# eSolderControl_v3.net
KiCad netlist of a schematic drawn in Altium Designer
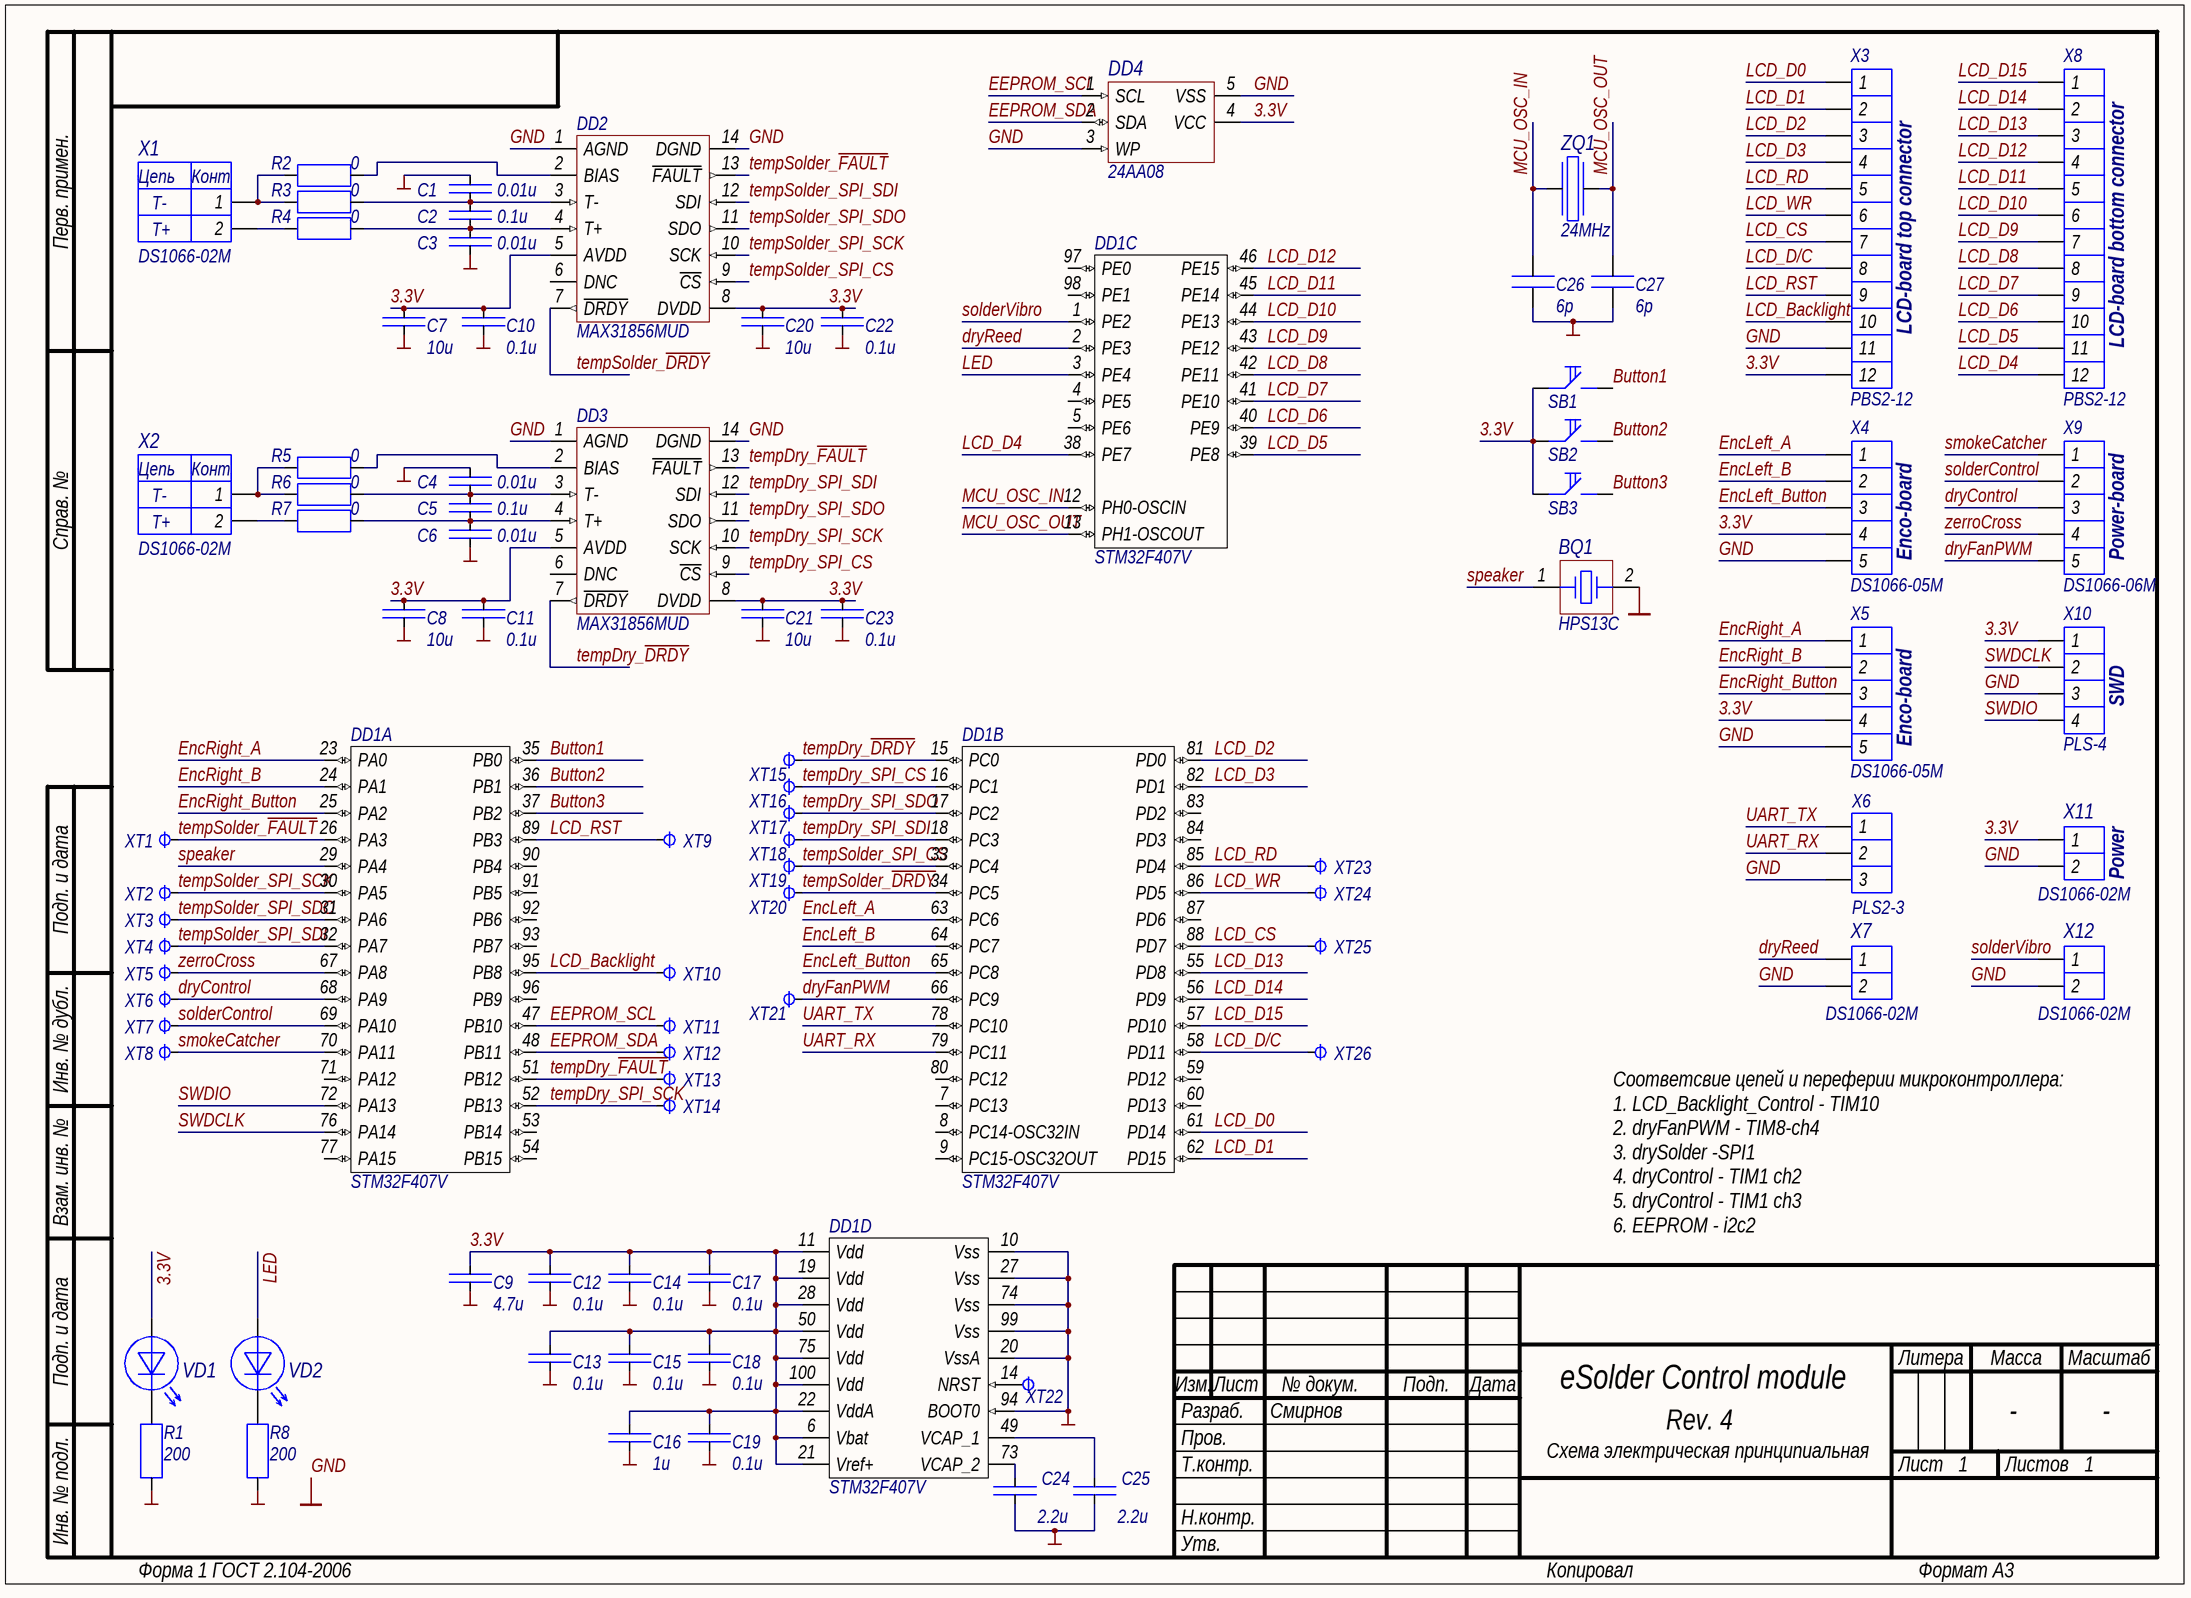
[diagram p0: eSolderControl_v3.SchDoc]

(export (version "E")
  (design (tool "Eeschema 10.0.6"))
  (components
    (comp (ref "BQ1")
      (value "HPS13C")
      (footprint "speaker:HPS13C")
      (libsource (lib "speaker") (part "Buzzer"))
    )
    (comp (ref "C1")
      (value "0.01u")
      (footprint "CapSMD:C0603")
      (libsource (lib "Capasitors") (part "Capasitor"))
    )
    (comp (ref "C2")
      (value "0.1u")
      (footprint "CapSMD:C0603")
      (libsource (lib "Capasitors") (part "Capasitor"))
    )
    (comp (ref "C3")
      (value "0.01u")
      (footprint "CapSMD:C0603")
      (libsource (lib "Capasitors") (part "Capasitor"))
    )
    (comp (ref "C4")
      (value "0.01u")
      (footprint "CapSMD:C0603")
      (libsource (lib "Capasitors") (part "Capasitor"))
    )
    (comp (ref "C5")
      (value "0.1u")
      (footprint "CapSMD:C0603")
      (libsource (lib "Capasitors") (part "Capasitor"))
    )
    (comp (ref "C6")
      (value "0.01u")
      (footprint "CapSMD:C0603")
      (libsource (lib "Capasitors") (part "Capasitor"))
    )
    (comp (ref "C7")
      (value "10u")
      (footprint "CapSMD:C0603")
      (libsource (lib "Capasitors") (part "Capasitor"))
    )
    (comp (ref "C8")
      (value "10u")
      (footprint "CapSMD:C0603")
      (libsource (lib "Capasitors") (part "Capasitor"))
    )
    (comp (ref "C9")
      (value "4.7u")
      (footprint "CapSMD:C0603")
      (libsource (lib "Capasitors") (part "Capasitor"))
    )
    (comp (ref "C10")
      (value "0.1u")
      (footprint "CapSMD:C0603")
      (libsource (lib "Capasitors") (part "Capasitor"))
    )
    (comp (ref "C11")
      (value "0.1u")
      (footprint "CapSMD:C0603")
      (libsource (lib "Capasitors") (part "Capasitor"))
    )
    (comp (ref "C12")
      (value "0.1u")
      (footprint "CapSMD:C0603")
      (libsource (lib "Capasitors") (part "Capasitor"))
    )
    (comp (ref "C13")
      (value "0.1u")
      (footprint "CapSMD:C0603")
      (libsource (lib "Capasitors") (part "Capasitor"))
    )
    (comp (ref "C14")
      (value "0.1u")
      (footprint "CapSMD:C0603")
      (libsource (lib "Capasitors") (part "Capasitor"))
    )
    (comp (ref "C15")
      (value "0.1u")
      (footprint "CapSMD:C0603")
      (libsource (lib "Capasitors") (part "Capasitor"))
    )
    (comp (ref "C16")
      (value "1u")
      (footprint "CapSMD:C0603")
      (libsource (lib "Capasitors") (part "Capasitor"))
    )
    (comp (ref "C17")
      (value "0.1u")
      (footprint "CapSMD:C0603")
      (libsource (lib "Capasitors") (part "Capasitor"))
    )
    (comp (ref "C18")
      (value "0.1u")
      (footprint "CapSMD:C0603")
      (libsource (lib "Capasitors") (part "Capasitor"))
    )
    (comp (ref "C19")
      (value "0.1u")
      (footprint "CapSMD:C0603")
      (libsource (lib "Capasitors") (part "Capasitor"))
    )
    (comp (ref "C20")
      (value "10u")
      (footprint "CapSMD:C0603")
      (libsource (lib "Capasitors") (part "Capasitor"))
    )
    (comp (ref "C21")
      (value "10u")
      (footprint "CapSMD:C0603")
      (libsource (lib "Capasitors") (part "Capasitor"))
    )
    (comp (ref "C22")
      (value "0.1u")
      (footprint "CapSMD:C0603")
      (libsource (lib "Capasitors") (part "Capasitor"))
    )
    (comp (ref "C23")
      (value "0.1u")
      (footprint "CapSMD:C0603")
      (libsource (lib "Capasitors") (part "Capasitor"))
    )
    (comp (ref "C24")
      (value "2.2u")
      (footprint "CapSMD:C0603")
      (libsource (lib "Capasitors") (part "Capasitor"))
    )
    (comp (ref "C25")
      (value "2.2u")
      (footprint "CapSMD:C0603")
      (libsource (lib "Capasitors") (part "Capasitor"))
    )
    (comp (ref "C26") (value "6p") (footprint "CapSMD:C0603") (libsource (lib "") (part "Capasitor_1")))
    (comp (ref "C27") (value "6p") (footprint "CapSMD:C0603") (libsource (lib "") (part "Capasitor_1")))
    (comp (ref "DD1")
      (value "STM32F407V")
      (footprint "STM32:LQFP100")
      (description "100pins, 168MHz")
      (libsource (lib "STM32") (part "STM32F407V"))
    )
    (comp (ref "DD2")
      (value "MAX31856MUD")
      (footprint "TSSOP:TSSOP65P640X120-14N")
      (libsource (lib "ThermocoupleDrv") (part "MAX31856MUD"))
    )
    (comp (ref "DD3")
      (value "MAX31856MUD")
      (footprint "TSSOP:TSSOP65P640X120-14N")
      (libsource (lib "ThermocoupleDrv") (part "MAX31856MUD"))
    )
    (comp (ref "DD4")
      (value "24AA08")
      (footprint "SOT23:SOT95P245X145-5N")
      (description "8K I2C Serial EEPROM")
      (libsource (lib "eeprom") (part "24AA08"))
    )
    (comp (ref "R1")
      (value "200")
      (footprint "ResistorSMD:R0603")
      (libsource (lib "Resistors") (part "Resistor"))
    )
    (comp (ref "R2")
      (value "0")
      (footprint "ResistorSMD:R0603")
      (libsource (lib "Resistors") (part "Resistor"))
    )
    (comp (ref "R3")
      (value "0")
      (footprint "ResistorSMD:R0603")
      (libsource (lib "Resistors") (part "Resistor"))
    )
    (comp (ref "R4")
      (value "0")
      (footprint "ResistorSMD:R0603")
      (libsource (lib "Resistors") (part "Resistor"))
    )
    (comp (ref "R5")
      (value "0")
      (footprint "ResistorSMD:R0603")
      (libsource (lib "Resistors") (part "Resistor"))
    )
    (comp (ref "R6")
      (value "0")
      (footprint "ResistorSMD:R0603")
      (libsource (lib "Resistors") (part "Resistor"))
    )
    (comp (ref "R7")
      (value "0")
      (footprint "ResistorSMD:R0603")
      (libsource (lib "Resistors") (part "Resistor"))
    )
    (comp (ref "R8")
      (value "200")
      (footprint "ResistorSMD:R0603")
      (libsource (lib "Resistors") (part "Resistor"))
    )
    (comp (ref "SB1") (value "*") (footprint "Buttons:TS_6x6") (libsource (lib "Buttons") (part "Button")))
    (comp (ref "SB2") (value "*") (footprint "Buttons:TS_6x6") (libsource (lib "Buttons") (part "Button")))
    (comp (ref "SB3") (value "*") (footprint "Buttons:TS_6x6") (libsource (lib "Buttons") (part "Button")))
    (comp (ref "VD1") (value "*") (footprint "Led:LED 0603_Green") (libsource (lib "LED") (part "LED")))
    (comp (ref "VD2") (value "*") (footprint "Led:LED 0603_RED") (libsource (lib "LED") (part "LED")))
    (comp (ref "X1")
      (value "DS1066-02M")
      (footprint "Connectors:DS1066-02M")
      (libsource (lib "Connectors") (part "2-PIN"))
    )
    (comp (ref "X2")
      (value "DS1066-02M")
      (footprint "Connectors:DS1066-02M")
      (libsource (lib "Connectors") (part "2-PIN"))
    )
    (comp (ref "X3")
      (value "PBS2-12")
      (footprint "Connectors:PBS2-12")
      (libsource (lib "Connectors") (part "12-PIN"))
    )
    (comp (ref "X4")
      (value "DS1066-05M")
      (footprint "Connectors:DS1066-05M")
      (libsource (lib "Connectors") (part "5-PIN"))
    )
    (comp (ref "X5")
      (value "DS1066-05M")
      (footprint "Connectors:DS1066-05M")
      (libsource (lib "Connectors") (part "5-PIN"))
    )
    (comp (ref "X6")
      (value "PLS2-3")
      (footprint "Connectors:PLS2-3")
      (libsource (lib "Connectors") (part "3-PIN"))
    )
    (comp (ref "X7")
      (value "DS1066-02M")
      (footprint "Connectors:DS1066-02M")
      (libsource (lib "Connectors") (part "2-PIN"))
    )
    (comp (ref "X8")
      (value "PBS2-12")
      (footprint "Connectors:PBS2-12")
      (libsource (lib "Connectors") (part "12-PIN"))
    )
    (comp (ref "X9")
      (value "DS1066-06M")
      (footprint "Connectors:DS1066-05M")
      (libsource (lib "Connectors") (part "5-PIN"))
    )
    (comp (ref "X10")
      (value "PLS-4")
      (footprint "Connectors:PLS-4")
      (libsource (lib "Connectors") (part "4-PIN"))
    )
    (comp (ref "X11")
      (value "DS1066-02M")
      (footprint "Connectors:DS1066-02M")
      (libsource (lib "Connectors") (part "2-PIN"))
    )
    (comp (ref "X12")
      (value "DS1066-02M")
      (footprint "Connectors:DS1066-02M")
      (libsource (lib "Connectors") (part "2-PIN"))
    )
    (comp (ref "XT1")
      (value "CheckPoint")
      (footprint "CheckPoint:CheckPoint_2mm")
      (libsource (lib "checkPoint") (part "CheckPoint"))
    )
    (comp (ref "XT2")
      (value "CheckPoint")
      (footprint "CheckPoint:CheckPoint_2mm")
      (libsource (lib "checkPoint") (part "CheckPoint"))
    )
    (comp (ref "XT3")
      (value "CheckPoint")
      (footprint "CheckPoint:CheckPoint_2mm")
      (libsource (lib "checkPoint") (part "CheckPoint"))
    )
    (comp (ref "XT4")
      (value "CheckPoint")
      (footprint "CheckPoint:CheckPoint_2mm")
      (libsource (lib "checkPoint") (part "CheckPoint"))
    )
    (comp (ref "XT5")
      (value "CheckPoint")
      (footprint "CheckPoint:CheckPoint_2mm")
      (libsource (lib "checkPoint") (part "CheckPoint"))
    )
    (comp (ref "XT6")
      (value "CheckPoint")
      (footprint "CheckPoint:CheckPoint_2mm")
      (libsource (lib "checkPoint") (part "CheckPoint"))
    )
    (comp (ref "XT7")
      (value "CheckPoint")
      (footprint "CheckPoint:CheckPoint_2mm")
      (libsource (lib "checkPoint") (part "CheckPoint"))
    )
    (comp (ref "XT8")
      (value "CheckPoint")
      (footprint "CheckPoint:CheckPoint_2mm")
      (libsource (lib "checkPoint") (part "CheckPoint"))
    )
    (comp (ref "XT9")
      (value "CheckPoint")
      (footprint "CheckPoint:CheckPoint_2mm")
      (libsource (lib "checkPoint") (part "CheckPoint"))
    )
    (comp (ref "XT10")
      (value "CheckPoint")
      (footprint "CheckPoint:CheckPoint_2mm")
      (libsource (lib "checkPoint") (part "CheckPoint"))
    )
    (comp (ref "XT11")
      (value "CheckPoint")
      (footprint "CheckPoint:CheckPoint_2mm")
      (libsource (lib "checkPoint") (part "CheckPoint"))
    )
    (comp (ref "XT12")
      (value "CheckPoint")
      (footprint "CheckPoint:CheckPoint_2mm")
      (libsource (lib "checkPoint") (part "CheckPoint"))
    )
    (comp (ref "XT13")
      (value "CheckPoint")
      (footprint "CheckPoint:CheckPoint_2mm")
      (libsource (lib "checkPoint") (part "CheckPoint"))
    )
    (comp (ref "XT14")
      (value "CheckPoint")
      (footprint "CheckPoint:CheckPoint_2mm")
      (libsource (lib "checkPoint") (part "CheckPoint"))
    )
    (comp (ref "XT15")
      (value "CheckPoint")
      (footprint "CheckPoint:CheckPoint_2mm")
      (libsource (lib "checkPoint") (part "CheckPoint"))
    )
    (comp (ref "XT16")
      (value "CheckPoint")
      (footprint "CheckPoint:CheckPoint_2mm")
      (libsource (lib "checkPoint") (part "CheckPoint"))
    )
    (comp (ref "XT17")
      (value "CheckPoint")
      (footprint "CheckPoint:CheckPoint_2mm")
      (libsource (lib "checkPoint") (part "CheckPoint"))
    )
    (comp (ref "XT18")
      (value "CheckPoint")
      (footprint "CheckPoint:CheckPoint_2mm")
      (libsource (lib "checkPoint") (part "CheckPoint"))
    )
    (comp (ref "XT19")
      (value "CheckPoint")
      (footprint "CheckPoint:CheckPoint_2mm")
      (libsource (lib "checkPoint") (part "CheckPoint"))
    )
    (comp (ref "XT20")
      (value "CheckPoint")
      (footprint "CheckPoint:CheckPoint_2mm")
      (libsource (lib "checkPoint") (part "CheckPoint"))
    )
    (comp (ref "XT21")
      (value "CheckPoint")
      (footprint "CheckPoint:CheckPoint_2mm")
      (libsource (lib "checkPoint") (part "CheckPoint"))
    )
    (comp (ref "XT22")
      (value "CheckPoint")
      (footprint "CheckPoint:CheckPoint_2mm")
      (libsource (lib "checkPoint") (part "CheckPoint"))
    )
    (comp (ref "XT23")
      (value "CheckPoint")
      (footprint "CheckPoint:CheckPoint_2mm")
      (libsource (lib "checkPoint") (part "CheckPoint"))
    )
    (comp (ref "XT24")
      (value "CheckPoint")
      (footprint "CheckPoint:CheckPoint_2mm")
      (libsource (lib "checkPoint") (part "CheckPoint"))
    )
    (comp (ref "XT25")
      (value "CheckPoint")
      (footprint "CheckPoint:CheckPoint_2mm")
      (libsource (lib "checkPoint") (part "CheckPoint"))
    )
    (comp (ref "XT26")
      (value "CheckPoint")
      (footprint "CheckPoint:CheckPoint_2mm")
      (libsource (lib "checkPoint") (part "CheckPoint"))
    )
    (comp (ref "ZQ1")
      (value "24MHz")
      (footprint "Resonator:XRCGB_F_Z")
      (libsource (lib "Resonator") (part "Resonator"))
    )
  )
  (nets
    (net (code "1") (name "/3.3V") (class "Default")
      (node (ref "C10") (pin "2") (pinfunction "2_2") (pintype "power_in"))
      (node (ref "C11") (pin "2") (pinfunction "2_2") (pintype "power_in"))
      (node (ref "C12") (pin "2") (pinfunction "2_2") (pintype "power_in"))
      (node (ref "C13") (pin "2") (pinfunction "2_2") (pintype "power_in"))
      (node (ref "C14") (pin "2") (pinfunction "2_2") (pintype "power_in"))
      (node (ref "C15") (pin "2") (pinfunction "2_2") (pintype "power_in"))
      (node (ref "C16") (pin "2") (pinfunction "2_2") (pintype "power_in"))
      (node (ref "C17") (pin "2") (pinfunction "2_2") (pintype "power_in"))
      (node (ref "C18") (pin "2") (pinfunction "2_2") (pintype "power_in"))
      (node (ref "C19") (pin "2") (pinfunction "2_2") (pintype "power_in"))
      (node (ref "C20") (pin "2") (pinfunction "2_2") (pintype "power_in"))
      (node (ref "C21") (pin "2") (pinfunction "2_2") (pintype "power_in"))
      (node (ref "C22") (pin "2") (pinfunction "2_2") (pintype "power_in"))
      (node (ref "C23") (pin "2") (pinfunction "2_2") (pintype "power_in"))
      (node (ref "C7") (pin "2") (pinfunction "2_2") (pintype "power_in"))
      (node (ref "C8") (pin "2") (pinfunction "2_2") (pintype "power_in"))
      (node (ref "C9") (pin "2") (pinfunction "2_2") (pintype "power_in"))
      (node (ref "DD1") (pin "100") (pinfunction "Vdd_100") (pintype "power_in"))
      (node (ref "DD1") (pin "11") (pinfunction "Vdd_11") (pintype "power_in"))
      (node (ref "DD1") (pin "19") (pinfunction "Vdd_19") (pintype "power_in"))
      (node (ref "DD1") (pin "21") (pinfunction "Vref+_21") (pintype "power_in"))
      (node (ref "DD1") (pin "22") (pinfunction "VddA_22") (pintype "power_in"))
      (node (ref "DD1") (pin "28") (pinfunction "Vdd_28") (pintype "power_in"))
      (node (ref "DD1") (pin "50") (pinfunction "Vdd_50") (pintype "power_in"))
      (node (ref "DD1") (pin "6") (pinfunction "Vbat_6") (pintype "power_in"))
      (node (ref "DD1") (pin "75") (pinfunction "Vdd_75") (pintype "power_in"))
      (node (ref "DD2") (pin "5") (pinfunction "AVDD_5") (pintype "power_in"))
      (node (ref "DD2") (pin "8") (pinfunction "DVDD_8") (pintype "power_in"))
      (node (ref "DD3") (pin "5") (pinfunction "AVDD_5") (pintype "power_in"))
      (node (ref "DD3") (pin "8") (pinfunction "DVDD_8") (pintype "power_in"))
      (node (ref "DD4") (pin "4") (pinfunction "VCC_4") (pintype "power_in"))
      (node (ref "SB1") (pin "1") (pintype "passive"))
      (node (ref "SB2") (pin "1") (pintype "passive"))
      (node (ref "SB3") (pin "1") (pintype "passive"))
      (node (ref "VD1") (pin "1") (pinfunction "1_1") (pintype "passive"))
      (node (ref "X10") (pin "1") (pinfunction "1_1") (pintype "passive"))
      (node (ref "X11") (pin "1") (pinfunction "1_1") (pintype "passive"))
      (node (ref "X3") (pin "12") (pinfunction "12_12") (pintype "passive"))
      (node (ref "X4") (pin "4") (pinfunction "4_4") (pintype "passive"))
      (node (ref "X5") (pin "4") (pinfunction "4_4") (pintype "passive"))
    )
    (net (code "2") (name "/Button1") (class "Default")
      (node (ref "DD1") (pin "35") (pinfunction "PB0_35") (pintype "bidirectional"))
      (node (ref "SB1") (pin "2") (pintype "passive"))
    )
    (net (code "3") (name "/Button2") (class "Default")
      (node (ref "DD1") (pin "36") (pinfunction "PB1_36") (pintype "bidirectional"))
      (node (ref "SB2") (pin "2") (pintype "passive"))
    )
    (net (code "4") (name "/Button3") (class "Default")
      (node (ref "DD1") (pin "37") (pinfunction "PB2_37") (pintype "bidirectional"))
      (node (ref "SB3") (pin "2") (pintype "passive"))
    )
    (net (code "5") (name "/EEPROM_SCL") (class "Default")
      (node (ref "DD1") (pin "47") (pinfunction "PB10_47") (pintype "bidirectional"))
      (node (ref "DD4") (pin "1") (pinfunction "SCL_1") (pintype "input"))
      (node (ref "XT11") (pin "1") (pintype "passive"))
    )
    (net (code "6") (name "/EEPROM_SDA") (class "Default")
      (node (ref "DD1") (pin "48") (pinfunction "PB11_48") (pintype "bidirectional"))
      (node (ref "DD4") (pin "2") (pinfunction "SDA_2") (pintype "bidirectional"))
      (node (ref "XT12") (pin "1") (pintype "passive"))
    )
    (net (code "7") (name "/EncLeft_A") (class "Default")
      (node (ref "DD1") (pin "63") (pinfunction "PC6_63") (pintype "bidirectional"))
      (node (ref "X4") (pin "1") (pinfunction "1_1") (pintype "passive"))
    )
    (net (code "8") (name "/EncLeft_B") (class "Default")
      (node (ref "DD1") (pin "64") (pinfunction "PC7_64") (pintype "bidirectional"))
      (node (ref "X4") (pin "2") (pinfunction "2_2") (pintype "passive"))
    )
    (net (code "9") (name "/EncLeft_Button") (class "Default")
      (node (ref "DD1") (pin "65") (pinfunction "PC8_65") (pintype "bidirectional"))
      (node (ref "X4") (pin "3") (pinfunction "3_3") (pintype "passive"))
    )
    (net (code "10") (name "/EncRight_A") (class "Default")
      (node (ref "DD1") (pin "23") (pinfunction "PA0_23") (pintype "bidirectional"))
      (node (ref "X5") (pin "1") (pinfunction "1_1") (pintype "passive"))
    )
    (net (code "11") (name "/EncRight_B") (class "Default")
      (node (ref "DD1") (pin "24") (pinfunction "PA1_24") (pintype "bidirectional"))
      (node (ref "X5") (pin "2") (pinfunction "2_2") (pintype "passive"))
    )
    (net (code "12") (name "/EncRight_Button") (class "Default")
      (node (ref "DD1") (pin "25") (pinfunction "PA2_25") (pintype "bidirectional"))
      (node (ref "X5") (pin "3") (pinfunction "3_3") (pintype "passive"))
    )
    (net (code "13") (name "/LCD_Backlight") (class "Default")
      (node (ref "DD1") (pin "95") (pinfunction "PB8_95") (pintype "bidirectional"))
      (node (ref "X3") (pin "10") (pinfunction "10_10") (pintype "passive"))
      (node (ref "XT10") (pin "1") (pintype "passive"))
    )
    (net (code "14") (name "/LCD_CS") (class "Default")
      (node (ref "DD1") (pin "88") (pinfunction "PD7_88") (pintype "bidirectional"))
      (node (ref "X3") (pin "7") (pinfunction "7_7") (pintype "passive"))
      (node (ref "XT25") (pin "1") (pintype "passive"))
    )
    (net (code "15") (name "/LCD_D0") (class "Default")
      (node (ref "DD1") (pin "61") (pinfunction "PD14_61") (pintype "bidirectional"))
      (node (ref "X3") (pin "1") (pinfunction "1_1") (pintype "passive"))
    )
    (net (code "16") (name "/LCD_D1") (class "Default")
      (node (ref "DD1") (pin "62") (pinfunction "PD15_62") (pintype "bidirectional"))
      (node (ref "X3") (pin "2") (pinfunction "2_2") (pintype "passive"))
    )
    (net (code "17") (name "/LCD_D2") (class "Default")
      (node (ref "DD1") (pin "81") (pinfunction "PD0_81") (pintype "bidirectional"))
      (node (ref "X3") (pin "3") (pinfunction "3_3") (pintype "passive"))
    )
    (net (code "18") (name "/LCD_D3") (class "Default")
      (node (ref "DD1") (pin "82") (pinfunction "PD1_82") (pintype "bidirectional"))
      (node (ref "X3") (pin "4") (pinfunction "4_4") (pintype "passive"))
    )
    (net (code "19") (name "/LCD_D4") (class "Default")
      (node (ref "DD1") (pin "38") (pinfunction "PE7_38") (pintype "bidirectional"))
      (node (ref "X8") (pin "12") (pinfunction "12_12") (pintype "passive"))
    )
    (net (code "20") (name "/LCD_D5") (class "Default")
      (node (ref "DD1") (pin "39") (pinfunction "PE8_39") (pintype "bidirectional"))
      (node (ref "X8") (pin "11") (pinfunction "11_11") (pintype "passive"))
    )
    (net (code "21") (name "/LCD_D6") (class "Default")
      (node (ref "DD1") (pin "40") (pinfunction "PE9_40") (pintype "bidirectional"))
      (node (ref "X8") (pin "10") (pinfunction "10_10") (pintype "passive"))
    )
    (net (code "22") (name "/LCD_D7") (class "Default")
      (node (ref "DD1") (pin "41") (pinfunction "PE10_41") (pintype "bidirectional"))
      (node (ref "X8") (pin "9") (pinfunction "9_9") (pintype "passive"))
    )
    (net (code "23") (name "/LCD_D8") (class "Default")
      (node (ref "DD1") (pin "42") (pinfunction "PE11_42") (pintype "bidirectional"))
      (node (ref "X8") (pin "8") (pinfunction "8_8") (pintype "passive"))
    )
    (net (code "24") (name "/LCD_D9") (class "Default")
      (node (ref "DD1") (pin "43") (pinfunction "PE12_43") (pintype "bidirectional"))
      (node (ref "X8") (pin "7") (pinfunction "7_7") (pintype "passive"))
    )
    (net (code "25") (name "/LCD_D10") (class "Default")
      (node (ref "DD1") (pin "44") (pinfunction "PE13_44") (pintype "bidirectional"))
      (node (ref "X8") (pin "6") (pinfunction "6_6") (pintype "passive"))
    )
    (net (code "26") (name "/LCD_D11") (class "Default")
      (node (ref "DD1") (pin "45") (pinfunction "PE14_45") (pintype "bidirectional"))
      (node (ref "X8") (pin "5") (pinfunction "5_5") (pintype "passive"))
    )
    (net (code "27") (name "/LCD_D12") (class "Default")
      (node (ref "DD1") (pin "46") (pinfunction "PE15_46") (pintype "bidirectional"))
      (node (ref "X8") (pin "4") (pinfunction "4_4") (pintype "passive"))
    )
    (net (code "28") (name "/LCD_D13") (class "Default")
      (node (ref "DD1") (pin "55") (pinfunction "PD8_55") (pintype "bidirectional"))
      (node (ref "X8") (pin "3") (pinfunction "3_3") (pintype "passive"))
    )
    (net (code "29") (name "/LCD_D14") (class "Default")
      (node (ref "DD1") (pin "56") (pinfunction "PD9_56") (pintype "bidirectional"))
      (node (ref "X8") (pin "2") (pinfunction "2_2") (pintype "passive"))
    )
    (net (code "30") (name "/LCD_D15") (class "Default")
      (node (ref "DD1") (pin "57") (pinfunction "PD10_57") (pintype "bidirectional"))
      (node (ref "X8") (pin "1") (pinfunction "1_1") (pintype "passive"))
    )
    (net (code "31") (name "/LCD_D{slash}C") (class "Default")
      (node (ref "DD1") (pin "58") (pinfunction "PD11_58") (pintype "bidirectional"))
      (node (ref "X3") (pin "8") (pinfunction "8_8") (pintype "passive"))
      (node (ref "XT26") (pin "1") (pintype "passive"))
    )
    (net (code "32") (name "/LCD_RD") (class "Default")
      (node (ref "DD1") (pin "85") (pinfunction "PD4_85") (pintype "bidirectional"))
      (node (ref "X3") (pin "5") (pinfunction "5_5") (pintype "passive"))
      (node (ref "XT23") (pin "1") (pintype "passive"))
    )
    (net (code "33") (name "/LCD_RST") (class "Default")
      (node (ref "DD1") (pin "89") (pinfunction "PB3_89") (pintype "bidirectional"))
      (node (ref "X3") (pin "9") (pinfunction "9_9") (pintype "passive"))
      (node (ref "XT9") (pin "1") (pintype "passive"))
    )
    (net (code "34") (name "/LCD_WR") (class "Default")
      (node (ref "DD1") (pin "86") (pinfunction "PD5_86") (pintype "bidirectional"))
      (node (ref "X3") (pin "6") (pinfunction "6_6") (pintype "passive"))
      (node (ref "XT24") (pin "1") (pintype "passive"))
    )
    (net (code "35") (name "/LED") (class "Default")
      (node (ref "DD1") (pin "3") (pinfunction "PE4_3") (pintype "bidirectional"))
      (node (ref "VD2") (pin "1") (pinfunction "1_1") (pintype "passive"))
    )
    (net (code "36") (name "/MCU_OSC_IN") (class "Default")
      (node (ref "C26") (pin "2") (pinfunction "2_2") (pintype "passive"))
      (node (ref "DD1") (pin "12") (pinfunction "PH0-OSCIN_12") (pintype "bidirectional"))
      (node (ref "ZQ1") (pin "1") (pintype "passive"))
    )
    (net (code "37") (name "/MCU_OSC_OUT") (class "Default")
      (node (ref "C27") (pin "2") (pinfunction "2_2") (pintype "passive"))
      (node (ref "DD1") (pin "13") (pinfunction "PH1-OSCOUT_13") (pintype "bidirectional"))
      (node (ref "ZQ1") (pin "2") (pintype "passive"))
    )
    (net (code "38") (name "/SWDCLK") (class "Default")
      (node (ref "DD1") (pin "76") (pinfunction "PA14_76") (pintype "bidirectional"))
      (node (ref "X10") (pin "2") (pinfunction "2_2") (pintype "passive"))
    )
    (net (code "39") (name "/SWDIO") (class "Default")
      (node (ref "DD1") (pin "72") (pinfunction "PA13_72") (pintype "bidirectional"))
      (node (ref "X10") (pin "4") (pinfunction "4_4") (pintype "passive"))
    )
    (net (code "40") (name "/UART_RX") (class "Default")
      (node (ref "DD1") (pin "79") (pinfunction "PC11_79") (pintype "bidirectional"))
      (node (ref "X6") (pin "2") (pinfunction "2_2") (pintype "passive"))
    )
    (net (code "41") (name "/UART_TX") (class "Default")
      (node (ref "DD1") (pin "78") (pinfunction "PC10_78") (pintype "bidirectional"))
      (node (ref "X6") (pin "1") (pinfunction "1_1") (pintype "passive"))
    )
    (net (code "42") (name "/dryControl") (class "Default")
      (node (ref "DD1") (pin "68") (pinfunction "PA9_68") (pintype "bidirectional"))
      (node (ref "X9") (pin "3") (pinfunction "3_3") (pintype "passive"))
      (node (ref "XT6") (pin "1") (pintype "passive"))
    )
    (net (code "43") (name "/dryFanPWM") (class "Default")
      (node (ref "DD1") (pin "66") (pinfunction "PC9_66") (pintype "bidirectional"))
      (node (ref "X9") (pin "5") (pinfunction "5_5") (pintype "passive"))
      (node (ref "XT21") (pin "1") (pintype "passive"))
    )
    (net (code "44") (name "/dryReed") (class "Default")
      (node (ref "DD1") (pin "2") (pinfunction "PE3_2") (pintype "bidirectional"))
      (node (ref "X7") (pin "1") (pinfunction "1_1") (pintype "passive"))
    )
    (net (code "45") (name "/smokeCatcher") (class "Default")
      (node (ref "DD1") (pin "70") (pinfunction "PA11_70") (pintype "bidirectional"))
      (node (ref "X9") (pin "1") (pinfunction "1_1") (pintype "passive"))
      (node (ref "XT8") (pin "1") (pintype "passive"))
    )
    (net (code "46") (name "/solderControl") (class "Default")
      (node (ref "DD1") (pin "69") (pinfunction "PA10_69") (pintype "bidirectional"))
      (node (ref "X9") (pin "2") (pinfunction "2_2") (pintype "passive"))
      (node (ref "XT7") (pin "1") (pintype "passive"))
    )
    (net (code "47") (name "/solderVibro") (class "Default")
      (node (ref "DD1") (pin "1") (pinfunction "PE2_1") (pintype "bidirectional"))
      (node (ref "X12") (pin "1") (pinfunction "1_1") (pintype "passive"))
    )
    (net (code "48") (name "/speaker") (class "Default")
      (node (ref "BQ1") (pin "1") (pintype "passive"))
      (node (ref "DD1") (pin "29") (pinfunction "PA4_29") (pintype "bidirectional"))
    )
    (net (code "49") (name "/tempDry_SPI_CS") (class "Default")
      (node (ref "DD1") (pin "16") (pinfunction "PC1_16") (pintype "bidirectional"))
      (node (ref "DD3") (pin "9") (pinfunction "~{CS}_9") (pintype "input"))
      (node (ref "XT16") (pin "1") (pintype "passive"))
    )
    (net (code "50") (name "/tempDry_SPI_SCK") (class "Default")
      (node (ref "DD1") (pin "52") (pinfunction "PB13_52") (pintype "bidirectional"))
      (node (ref "DD3") (pin "10") (pinfunction "SCK_10") (pintype "input"))
      (node (ref "XT14") (pin "1") (pintype "passive"))
    )
    (net (code "51") (name "/tempDry_SPI_SDI") (class "Default")
      (node (ref "DD1") (pin "18") (pinfunction "PC3_18") (pintype "bidirectional"))
      (node (ref "DD3") (pin "12") (pinfunction "SDI_12") (pintype "input"))
      (node (ref "XT18") (pin "1") (pintype "passive"))
    )
    (net (code "52") (name "/tempDry_SPI_SDO") (class "Default")
      (node (ref "DD1") (pin "17") (pinfunction "PC2_17") (pintype "bidirectional"))
      (node (ref "DD3") (pin "11") (pinfunction "SDO_11") (pintype "output"))
      (node (ref "XT17") (pin "1") (pintype "passive"))
    )
    (net (code "53") (name "/tempDry_~{DRDY}") (class "Default")
      (node (ref "DD1") (pin "15") (pinfunction "PC0_15") (pintype "bidirectional"))
      (node (ref "DD3") (pin "7") (pinfunction "~{DRDY}_7") (pintype "output"))
      (node (ref "XT15") (pin "1") (pintype "passive"))
    )
    (net (code "54") (name "/tempDry_~{FAULT}") (class "Default")
      (node (ref "DD1") (pin "51") (pinfunction "PB12_51") (pintype "bidirectional"))
      (node (ref "DD3") (pin "13") (pinfunction "~{FAULT}_13") (pintype "output"))
      (node (ref "XT13") (pin "1") (pintype "passive"))
    )
    (net (code "55") (name "/tempSolder_SPI_CS") (class "Default")
      (node (ref "DD1") (pin "33") (pinfunction "PC4_33") (pintype "bidirectional"))
      (node (ref "DD2") (pin "9") (pinfunction "~{CS}_9") (pintype "input"))
      (node (ref "XT19") (pin "1") (pintype "passive"))
    )
    (net (code "56") (name "/tempSolder_SPI_SCK") (class "Default")
      (node (ref "DD1") (pin "30") (pinfunction "PA5_30") (pintype "bidirectional"))
      (node (ref "DD2") (pin "10") (pinfunction "SCK_10") (pintype "input"))
      (node (ref "XT2") (pin "1") (pintype "passive"))
    )
    (net (code "57") (name "/tempSolder_SPI_SDI") (class "Default")
      (node (ref "DD1") (pin "32") (pinfunction "PA7_32") (pintype "bidirectional"))
      (node (ref "DD2") (pin "12") (pinfunction "SDI_12") (pintype "input"))
      (node (ref "XT4") (pin "1") (pintype "passive"))
    )
    (net (code "58") (name "/tempSolder_SPI_SDO") (class "Default")
      (node (ref "DD1") (pin "31") (pinfunction "PA6_31") (pintype "bidirectional"))
      (node (ref "DD2") (pin "11") (pinfunction "SDO_11") (pintype "output"))
      (node (ref "XT3") (pin "1") (pintype "passive"))
    )
    (net (code "59") (name "/tempSolder_~{DRDY}") (class "Default")
      (node (ref "DD1") (pin "34") (pinfunction "PC5_34") (pintype "bidirectional"))
      (node (ref "DD2") (pin "7") (pinfunction "~{DRDY}_7") (pintype "output"))
      (node (ref "XT20") (pin "1") (pintype "passive"))
    )
    (net (code "60") (name "/tempSolder_~{FAULT}") (class "Default")
      (node (ref "DD1") (pin "26") (pinfunction "PA3_26") (pintype "bidirectional"))
      (node (ref "DD2") (pin "13") (pinfunction "~{FAULT}_13") (pintype "output"))
      (node (ref "XT1") (pin "1") (pintype "passive"))
    )
    (net (code "61") (name "/zerroCross") (class "Default")
      (node (ref "DD1") (pin "67") (pinfunction "PA8_67") (pintype "bidirectional"))
      (node (ref "X9") (pin "4") (pinfunction "4_4") (pintype "passive"))
      (node (ref "XT5") (pin "1") (pintype "passive"))
    )
    (net (code "62") (name "GND") (class "Default")
      (node (ref "BQ1") (pin "2") (pintype "passive"))
      (node (ref "C26") (pin "1") (pinfunction "1_1") (pintype "passive"))
      (node (ref "C27") (pin "1") (pinfunction "1_1") (pintype "passive"))
      (node (ref "DD2") (pin "1") (pinfunction "AGND_1") (pintype "power_in"))
      (node (ref "DD2") (pin "14") (pinfunction "DGND_14") (pintype "power_in"))
      (node (ref "DD3") (pin "1") (pinfunction "AGND_1") (pintype "power_in"))
      (node (ref "DD3") (pin "14") (pinfunction "DGND_14") (pintype "power_in"))
      (node (ref "DD4") (pin "3") (pinfunction "WP_3") (pintype "input"))
      (node (ref "DD4") (pin "5") (pinfunction "VSS_5") (pintype "power_in"))
      (node (ref "R1") (pin "2") (pinfunction "2_2") (pintype "passive"))
      (node (ref "R8") (pin "2") (pinfunction "2_2") (pintype "passive"))
      (node (ref "X10") (pin "3") (pinfunction "3_3") (pintype "passive"))
      (node (ref "X11") (pin "2") (pinfunction "2_2") (pintype "passive"))
      (node (ref "X12") (pin "2") (pinfunction "2_2") (pintype "passive"))
      (node (ref "X3") (pin "11") (pinfunction "11_11") (pintype "passive"))
      (node (ref "X4") (pin "5") (pinfunction "5_5") (pintype "passive"))
      (node (ref "X5") (pin "5") (pinfunction "5_5") (pintype "passive"))
      (node (ref "X6") (pin "3") (pinfunction "3_3") (pintype "passive"))
      (node (ref "X7") (pin "2") (pinfunction "2_2") (pintype "passive"))
    )
    (net (code "63") (name "Net-(DD1D-NRST)") (class "Default")
      (node (ref "DD1") (pin "14") (pinfunction "NRST_14") (pintype "input"))
      (node (ref "XT22") (pin "1") (pintype "passive"))
    )
    (net (code "64") (name "Net-(DD1D-VCAP_1)") (class "Default")
      (node (ref "C25") (pin "2") (pinfunction "2_2") (pintype "power_in"))
      (node (ref "DD1") (pin "49") (pinfunction "VCAP_1_49") (pintype "power_in"))
    )
    (net (code "65") (name "Net-(DD1D-VCAP_2)") (class "Default")
      (node (ref "C24") (pin "1") (pinfunction "1_1") (pintype "power_in"))
      (node (ref "DD1") (pin "73") (pinfunction "VCAP_2_73") (pintype "power_in"))
    )
    (net (code "66") (name "Net-(DD2-BIAS)") (class "Default")
      (node (ref "DD2") (pin "2") (pinfunction "BIAS_2") (pintype "passive"))
      (node (ref "R2") (pin "2") (pinfunction "2_2") (pintype "passive"))
    )
    (net (code "67") (name "Net-(DD2-T+)") (class "Default")
      (node (ref "C2") (pin "1") (pinfunction "1_1") (pintype "power_in"))
      (node (ref "C3") (pin "2") (pinfunction "2_2") (pintype "power_in"))
      (node (ref "DD2") (pin "4") (pinfunction "T+_4") (pintype "input"))
      (node (ref "R4") (pin "2") (pinfunction "2_2") (pintype "passive"))
    )
    (net (code "68") (name "Net-(DD2-T-)") (class "Default")
      (node (ref "C1") (pin "1") (pinfunction "1_1") (pintype "power_in"))
      (node (ref "C2") (pin "2") (pinfunction "2_2") (pintype "power_in"))
      (node (ref "DD2") (pin "3") (pinfunction "T-_3") (pintype "input"))
      (node (ref "R3") (pin "2") (pinfunction "2_2") (pintype "passive"))
    )
    (net (code "69") (name "Net-(DD3-BIAS)") (class "Default")
      (node (ref "DD3") (pin "2") (pinfunction "BIAS_2") (pintype "passive"))
      (node (ref "R5") (pin "2") (pinfunction "2_2") (pintype "passive"))
    )
    (net (code "70") (name "Net-(DD3-T+)") (class "Default")
      (node (ref "C5") (pin "1") (pinfunction "1_1") (pintype "power_in"))
      (node (ref "C6") (pin "2") (pinfunction "2_2") (pintype "power_in"))
      (node (ref "DD3") (pin "4") (pinfunction "T+_4") (pintype "input"))
      (node (ref "R7") (pin "2") (pinfunction "2_2") (pintype "passive"))
    )
    (net (code "71") (name "Net-(DD3-T-)") (class "Default")
      (node (ref "C4") (pin "1") (pinfunction "1_1") (pintype "power_in"))
      (node (ref "C5") (pin "2") (pinfunction "2_2") (pintype "power_in"))
      (node (ref "DD3") (pin "3") (pinfunction "T-_3") (pintype "input"))
      (node (ref "R6") (pin "2") (pinfunction "2_2") (pintype "passive"))
    )
    (net (code "72") (name "Net-(R1-Pad1)") (class "Default")
      (node (ref "R1") (pin "1") (pinfunction "1_1") (pintype "passive"))
      (node (ref "VD1") (pin "2") (pinfunction "2_2") (pintype "passive"))
    )
    (net (code "73") (name "Net-(R2-Pad1)") (class "Default")
      (node (ref "R2") (pin "1") (pinfunction "1_1") (pintype "passive"))
      (node (ref "R3") (pin "1") (pinfunction "1_1") (pintype "passive"))
      (node (ref "X1") (pin "1") (pinfunction "1_1") (pintype "passive"))
    )
    (net (code "74") (name "Net-(R4-Pad1)") (class "Default")
      (node (ref "R4") (pin "1") (pinfunction "1_1") (pintype "passive"))
      (node (ref "X1") (pin "2") (pinfunction "2_2") (pintype "passive"))
    )
    (net (code "75") (name "Net-(R5-Pad1)") (class "Default")
      (node (ref "R5") (pin "1") (pinfunction "1_1") (pintype "passive"))
      (node (ref "R6") (pin "1") (pinfunction "1_1") (pintype "passive"))
      (node (ref "X2") (pin "1") (pinfunction "1_1") (pintype "passive"))
    )
    (net (code "76") (name "Net-(R7-Pad1)") (class "Default")
      (node (ref "R7") (pin "1") (pinfunction "1_1") (pintype "passive"))
      (node (ref "X2") (pin "2") (pinfunction "2_2") (pintype "passive"))
    )
    (net (code "77") (name "Net-(R8-Pad1)") (class "Default")
      (node (ref "R8") (pin "1") (pinfunction "1_1") (pintype "passive"))
      (node (ref "VD2") (pin "2") (pinfunction "2_2") (pintype "passive"))
    )
    (net (code "78") (name "VCC") (class "Default")
      (node (ref "C1") (pin "2") (pinfunction "2_2") (pintype "power_in"))
      (node (ref "C10") (pin "1") (pinfunction "1_1") (pintype "power_in"))
      (node (ref "C11") (pin "1") (pinfunction "1_1") (pintype "power_in"))
      (node (ref "C12") (pin "1") (pinfunction "1_1") (pintype "power_in"))
      (node (ref "C13") (pin "1") (pinfunction "1_1") (pintype "power_in"))
      (node (ref "C14") (pin "1") (pinfunction "1_1") (pintype "power_in"))
      (node (ref "C15") (pin "1") (pinfunction "1_1") (pintype "power_in"))
      (node (ref "C16") (pin "1") (pinfunction "1_1") (pintype "power_in"))
      (node (ref "C17") (pin "1") (pinfunction "1_1") (pintype "power_in"))
      (node (ref "C18") (pin "1") (pinfunction "1_1") (pintype "power_in"))
      (node (ref "C19") (pin "1") (pinfunction "1_1") (pintype "power_in"))
      (node (ref "C20") (pin "1") (pinfunction "1_1") (pintype "power_in"))
      (node (ref "C21") (pin "1") (pinfunction "1_1") (pintype "power_in"))
      (node (ref "C22") (pin "1") (pinfunction "1_1") (pintype "power_in"))
      (node (ref "C23") (pin "1") (pinfunction "1_1") (pintype "power_in"))
      (node (ref "C24") (pin "2") (pinfunction "2_2") (pintype "power_in"))
      (node (ref "C25") (pin "1") (pinfunction "1_1") (pintype "power_in"))
      (node (ref "C3") (pin "1") (pinfunction "1_1") (pintype "power_in"))
      (node (ref "C4") (pin "2") (pinfunction "2_2") (pintype "power_in"))
      (node (ref "C6") (pin "1") (pinfunction "1_1") (pintype "power_in"))
      (node (ref "C7") (pin "1") (pinfunction "1_1") (pintype "power_in"))
      (node (ref "C8") (pin "1") (pinfunction "1_1") (pintype "power_in"))
      (node (ref "C9") (pin "1") (pinfunction "1_1") (pintype "power_in"))
      (node (ref "DD1") (pin "10") (pinfunction "Vss_10") (pintype "power_in"))
      (node (ref "DD1") (pin "20") (pinfunction "VssA_20") (pintype "power_in"))
      (node (ref "DD1") (pin "27") (pinfunction "Vss_27") (pintype "power_in"))
      (node (ref "DD1") (pin "74") (pinfunction "Vss_74") (pintype "power_in"))
      (node (ref "DD1") (pin "94") (pinfunction "BOOT0_94") (pintype "input"))
      (node (ref "DD1") (pin "99") (pinfunction "Vss_99") (pintype "power_in"))
    )
    (net (code "79") (name "unconnected-(DD1A-PA12-Pad71)") (class "Default")
      (node (ref "DD1") (pin "71") (pinfunction "PA12_71") (pintype "bidirectional"))
    )
    (net (code "80") (name "unconnected-(DD1A-PA15-Pad77)") (class "Default")
      (node (ref "DD1") (pin "77") (pinfunction "PA15_77") (pintype "bidirectional"))
    )
    (net (code "81") (name "unconnected-(DD1A-PB4-Pad90)") (class "Default")
      (node (ref "DD1") (pin "90") (pinfunction "PB4_90") (pintype "bidirectional"))
    )
    (net (code "82") (name "unconnected-(DD1A-PB5-Pad91)") (class "Default")
      (node (ref "DD1") (pin "91") (pinfunction "PB5_91") (pintype "bidirectional"))
    )
    (net (code "83") (name "unconnected-(DD1A-PB6-Pad92)") (class "Default")
      (node (ref "DD1") (pin "92") (pinfunction "PB6_92") (pintype "bidirectional"))
    )
    (net (code "84") (name "unconnected-(DD1A-PB7-Pad93)") (class "Default")
      (node (ref "DD1") (pin "93") (pinfunction "PB7_93") (pintype "bidirectional"))
    )
    (net (code "85") (name "unconnected-(DD1A-PB9-Pad96)") (class "Default")
      (node (ref "DD1") (pin "96") (pinfunction "PB9_96") (pintype "bidirectional"))
    )
    (net (code "86") (name "unconnected-(DD1A-PB14-Pad53)") (class "Default")
      (node (ref "DD1") (pin "53") (pinfunction "PB14_53") (pintype "bidirectional"))
    )
    (net (code "87") (name "unconnected-(DD1A-PB15-Pad54)") (class "Default")
      (node (ref "DD1") (pin "54") (pinfunction "PB15_54") (pintype "bidirectional"))
    )
    (net (code "88") (name "unconnected-(DD1B-PC12-Pad80)") (class "Default")
      (node (ref "DD1") (pin "80") (pinfunction "PC12_80") (pintype "bidirectional"))
    )
    (net (code "89") (name "unconnected-(DD1B-PC13-Pad7)") (class "Default")
      (node (ref "DD1") (pin "7") (pinfunction "PC13_7") (pintype "bidirectional"))
    )
    (net (code "90") (name "unconnected-(DD1B-PC14-OSC32IN-Pad8)") (class "Default")
      (node (ref "DD1") (pin "8") (pinfunction "PC14-OSC32IN_8") (pintype "bidirectional"))
    )
    (net (code "91") (name "unconnected-(DD1B-PC15-OSC32OUT-Pad9)") (class "Default")
      (node (ref "DD1") (pin "9") (pinfunction "PC15-OSC32OUT_9") (pintype "bidirectional"))
    )
    (net (code "92") (name "unconnected-(DD1B-PD2-Pad83)") (class "Default")
      (node (ref "DD1") (pin "83") (pinfunction "PD2_83") (pintype "bidirectional"))
    )
    (net (code "93") (name "unconnected-(DD1B-PD3-Pad84)") (class "Default")
      (node (ref "DD1") (pin "84") (pinfunction "PD3_84") (pintype "bidirectional"))
    )
    (net (code "94") (name "unconnected-(DD1B-PD6-Pad87)") (class "Default")
      (node (ref "DD1") (pin "87") (pinfunction "PD6_87") (pintype "bidirectional"))
    )
    (net (code "95") (name "unconnected-(DD1B-PD12-Pad59)") (class "Default")
      (node (ref "DD1") (pin "59") (pinfunction "PD12_59") (pintype "bidirectional"))
    )
    (net (code "96") (name "unconnected-(DD1B-PD13-Pad60)") (class "Default")
      (node (ref "DD1") (pin "60") (pinfunction "PD13_60") (pintype "bidirectional"))
    )
    (net (code "97") (name "unconnected-(DD1C-PE0-Pad97)") (class "Default")
      (node (ref "DD1") (pin "97") (pinfunction "PE0_97") (pintype "bidirectional"))
    )
    (net (code "98") (name "unconnected-(DD1C-PE1-Pad98)") (class "Default")
      (node (ref "DD1") (pin "98") (pinfunction "PE1_98") (pintype "bidirectional"))
    )
    (net (code "99") (name "unconnected-(DD1C-PE5-Pad4)") (class "Default")
      (node (ref "DD1") (pin "4") (pinfunction "PE5_4") (pintype "bidirectional"))
    )
    (net (code "100") (name "unconnected-(DD1C-PE6-Pad5)") (class "Default")
      (node (ref "DD1") (pin "5") (pinfunction "PE6_5") (pintype "bidirectional"))
    )
    (net (code "101") (name "unconnected-(DD2-DNC-Pad6)") (class "Default")
      (node (ref "DD2") (pin "6") (pinfunction "DNC_6") (pintype "passive"))
    )
    (net (code "102") (name "unconnected-(DD3-DNC-Pad6)") (class "Default")
      (node (ref "DD3") (pin "6") (pinfunction "DNC_6") (pintype "passive"))
    )
  )
)
